# FRAM_with_level_converter_discrete.net
KiCad netlist of a schematic drawn in EAGLE
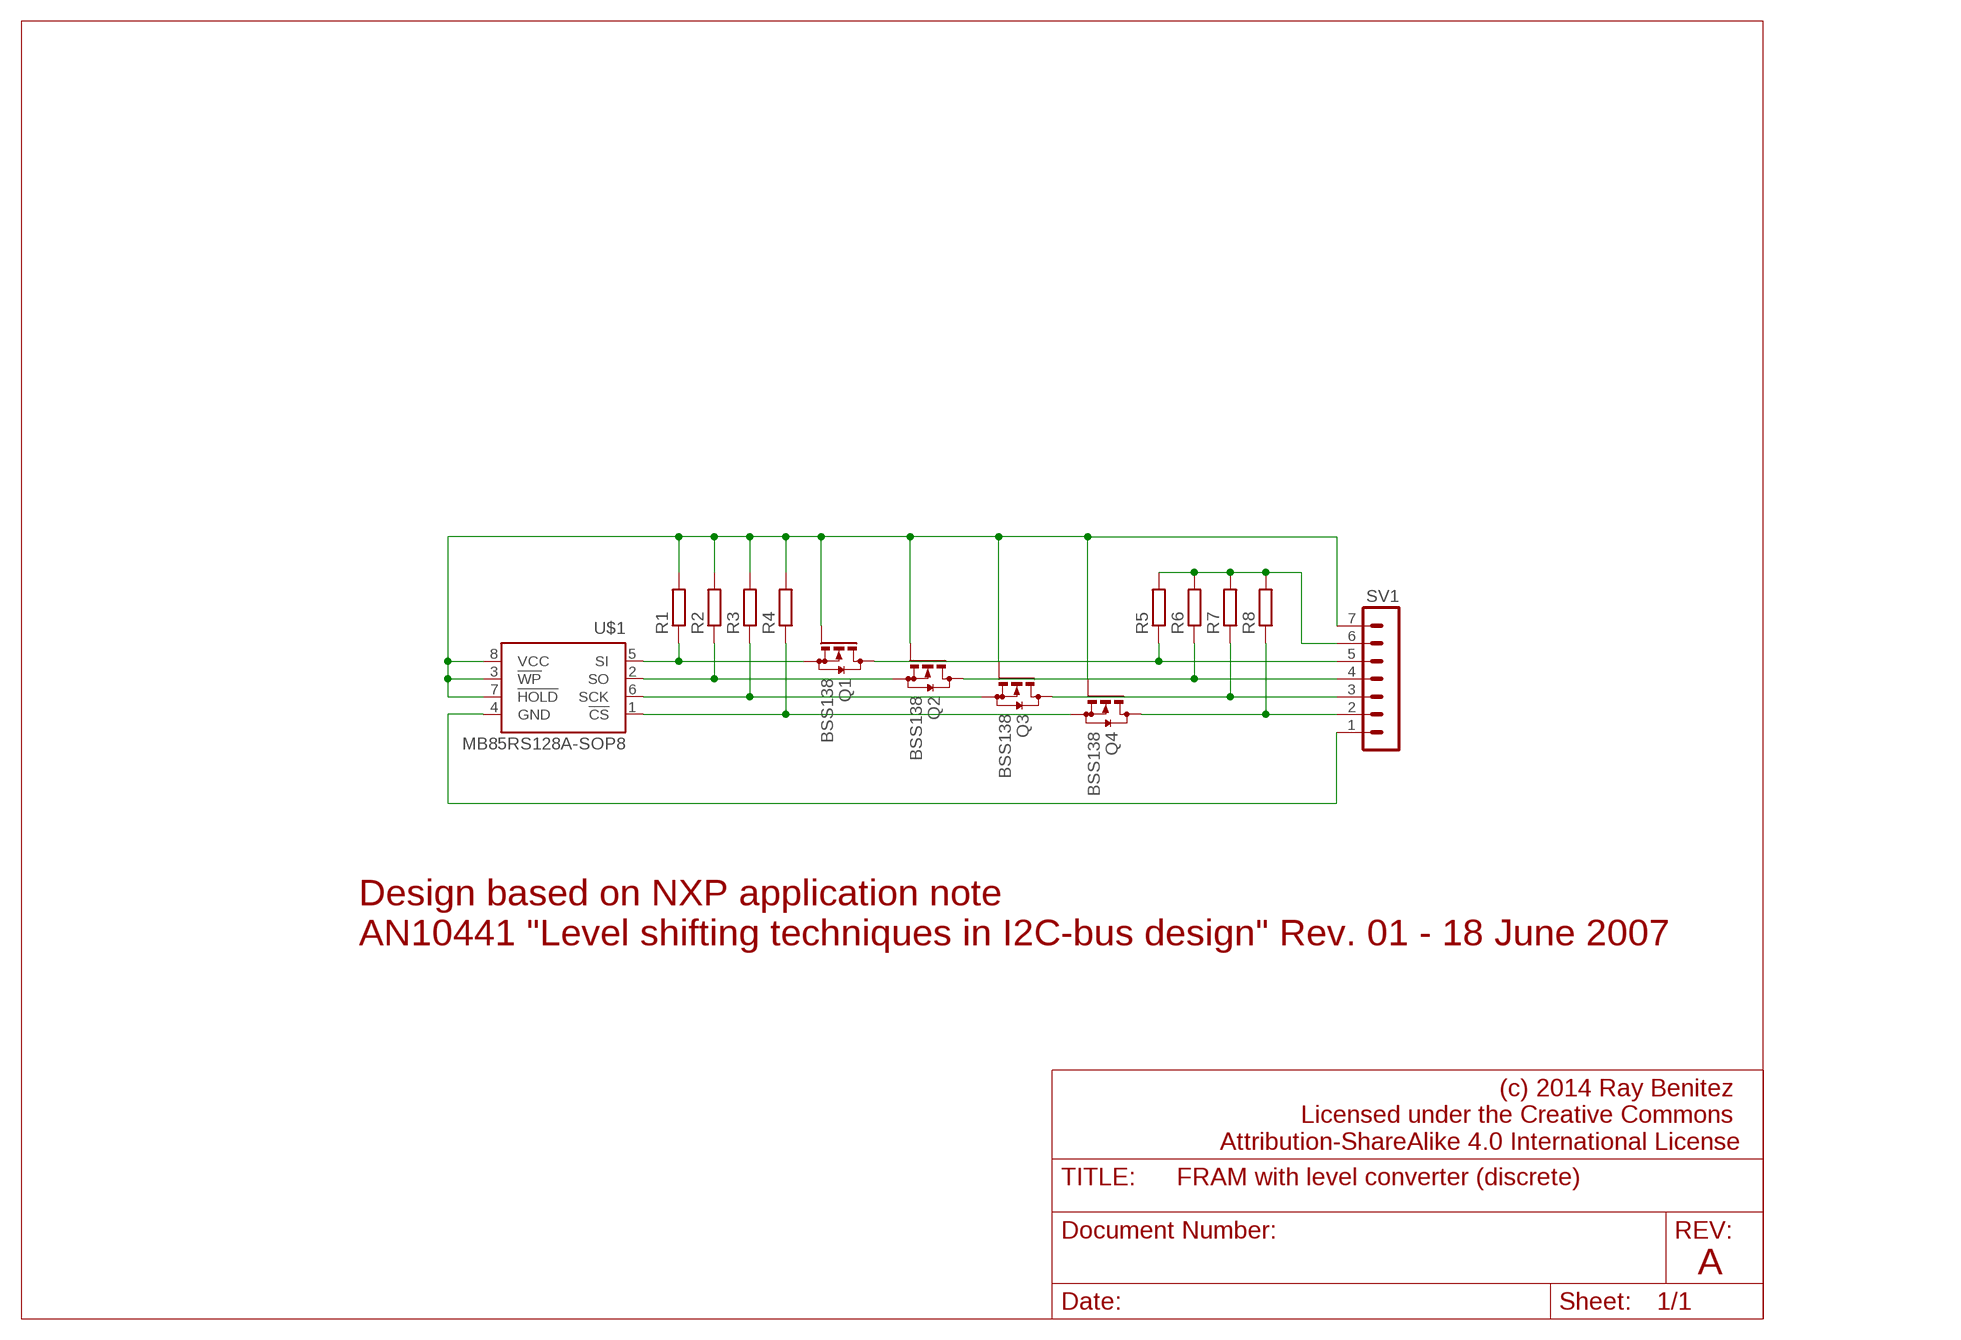
[diagram p0: schematic, sheet 1]

(export (version "E")
  (design (tool "Eeschema 10.0.6"))
  (components
    (comp (ref "Q1")
      (value "BSS138")
      (footprint "eagle-import:SOT23")
      (libsource (lib "eagle-import") (part "BSS138-SOT23"))
    )
    (comp (ref "Q2")
      (value "BSS138")
      (footprint "eagle-import:SOT23")
      (libsource (lib "eagle-import") (part "BSS138-SOT23"))
    )
    (comp (ref "Q3")
      (value "BSS138")
      (footprint "eagle-import:SOT23")
      (libsource (lib "eagle-import") (part "BSS138-SOT23"))
    )
    (comp (ref "Q4")
      (value "BSS138")
      (footprint "eagle-import:SOT23")
      (libsource (lib "eagle-import") (part "BSS138-SOT23"))
    )
    (comp (ref "R1")
      (value "R-EU_R0805")
      (footprint "eagle-import:R0805")
      (libsource (lib "eagle-import") (part "R-EU_R0805"))
    )
    (comp (ref "R2")
      (value "R-EU_R0805")
      (footprint "eagle-import:R0805")
      (libsource (lib "eagle-import") (part "R-EU_R0805"))
    )
    (comp (ref "R3")
      (value "R-EU_R0805")
      (footprint "eagle-import:R0805")
      (libsource (lib "eagle-import") (part "R-EU_R0805"))
    )
    (comp (ref "R4")
      (value "R-EU_R0805")
      (footprint "eagle-import:R0805")
      (libsource (lib "eagle-import") (part "R-EU_R0805"))
    )
    (comp (ref "R5")
      (value "R-EU_R0805")
      (footprint "eagle-import:R0805")
      (libsource (lib "eagle-import") (part "R-EU_R0805"))
    )
    (comp (ref "R6")
      (value "R-EU_R0805")
      (footprint "eagle-import:R0805")
      (libsource (lib "eagle-import") (part "R-EU_R0805"))
    )
    (comp (ref "R7")
      (value "R-EU_R0805")
      (footprint "eagle-import:R0805")
      (libsource (lib "eagle-import") (part "R-EU_R0805"))
    )
    (comp (ref "R8")
      (value "R-EU_R0805")
      (footprint "eagle-import:R0805")
      (libsource (lib "eagle-import") (part "R-EU_R0805"))
    )
    (comp (ref "SV1")
      (value "MA07-1")
      (footprint "eagle-import:MA07-1")
      (libsource (lib "eagle-import") (part "MA07-1"))
    )
    (comp (ref "U$1")
      (value "MB85RS128A-SOP8")
      (footprint "eagle-import:SO08")
      (libsource (lib "eagle-import") (part "MB85RS-SOP8128A"))
    )
  )
  (nets
    (net (code "1") (name "Net-(Q1-D)") (class "Default")
      (node (ref "Q1") (pin "3") (pinfunction "D_3") (pintype "passive"))
      (node (ref "R5") (pin "1") (pinfunction "1_1") (pintype "passive"))
      (node (ref "SV1") (pin "5") (pinfunction "5_5") (pintype "passive"))
    )
    (net (code "2") (name "Net-(Q1-G)") (class "Default")
      (node (ref "Q1") (pin "1") (pinfunction "G_1") (pintype "passive"))
      (node (ref "Q2") (pin "1") (pinfunction "G_1") (pintype "passive"))
      (node (ref "Q3") (pin "1") (pinfunction "G_1") (pintype "passive"))
      (node (ref "Q4") (pin "1") (pinfunction "G_1") (pintype "passive"))
      (node (ref "R1") (pin "2") (pinfunction "2_2") (pintype "passive"))
      (node (ref "R2") (pin "2") (pinfunction "2_2") (pintype "passive"))
      (node (ref "R3") (pin "2") (pinfunction "2_2") (pintype "passive"))
      (node (ref "R4") (pin "2") (pinfunction "2_2") (pintype "passive"))
      (node (ref "SV1") (pin "7") (pinfunction "7_7") (pintype "passive"))
      (node (ref "U$1") (pin "3") (pinfunction "~{WP}_3") (pintype "input"))
      (node (ref "U$1") (pin "7") (pinfunction "~{HOLD}_7") (pintype "input"))
      (node (ref "U$1") (pin "8") (pinfunction "VCC_8") (pintype "power_in"))
    )
    (net (code "3") (name "Net-(Q1-S)") (class "Default")
      (node (ref "Q1") (pin "2") (pinfunction "S_2") (pintype "passive"))
      (node (ref "R1") (pin "1") (pinfunction "1_1") (pintype "passive"))
      (node (ref "U$1") (pin "5") (pinfunction "SI_5") (pintype "input"))
    )
    (net (code "4") (name "Net-(Q2-D)") (class "Default")
      (node (ref "Q2") (pin "3") (pinfunction "D_3") (pintype "passive"))
      (node (ref "R6") (pin "1") (pinfunction "1_1") (pintype "passive"))
      (node (ref "SV1") (pin "4") (pinfunction "4_4") (pintype "passive"))
    )
    (net (code "5") (name "Net-(Q2-S)") (class "Default")
      (node (ref "Q2") (pin "2") (pinfunction "S_2") (pintype "passive"))
      (node (ref "R2") (pin "1") (pinfunction "1_1") (pintype "passive"))
      (node (ref "U$1") (pin "2") (pinfunction "SO_2") (pintype "output"))
    )
    (net (code "6") (name "Net-(Q3-D)") (class "Default")
      (node (ref "Q3") (pin "3") (pinfunction "D_3") (pintype "passive"))
      (node (ref "R7") (pin "1") (pinfunction "1_1") (pintype "passive"))
      (node (ref "SV1") (pin "3") (pinfunction "3_3") (pintype "passive"))
    )
    (net (code "7") (name "Net-(Q3-S)") (class "Default")
      (node (ref "Q3") (pin "2") (pinfunction "S_2") (pintype "passive"))
      (node (ref "R3") (pin "1") (pinfunction "1_1") (pintype "passive"))
      (node (ref "U$1") (pin "6") (pinfunction "SCK_6") (pintype "input"))
    )
    (net (code "8") (name "Net-(Q4-D)") (class "Default")
      (node (ref "Q4") (pin "3") (pinfunction "D_3") (pintype "passive"))
      (node (ref "R8") (pin "1") (pinfunction "1_1") (pintype "passive"))
      (node (ref "SV1") (pin "2") (pinfunction "2_2") (pintype "passive"))
    )
    (net (code "9") (name "Net-(Q4-S)") (class "Default")
      (node (ref "Q4") (pin "2") (pinfunction "S_2") (pintype "passive"))
      (node (ref "R4") (pin "1") (pinfunction "1_1") (pintype "passive"))
      (node (ref "U$1") (pin "1") (pinfunction "~{CS}_1") (pintype "input"))
    )
    (net (code "10") (name "Net-(R5-Pad2)") (class "Default")
      (node (ref "R5") (pin "2") (pinfunction "2_2") (pintype "passive"))
      (node (ref "R6") (pin "2") (pinfunction "2_2") (pintype "passive"))
      (node (ref "R7") (pin "2") (pinfunction "2_2") (pintype "passive"))
      (node (ref "R8") (pin "2") (pinfunction "2_2") (pintype "passive"))
      (node (ref "SV1") (pin "6") (pinfunction "6_6") (pintype "passive"))
    )
    (net (code "11") (name "Net-(U$1-GND)") (class "Default")
      (node (ref "SV1") (pin "1") (pinfunction "1_1") (pintype "passive"))
      (node (ref "U$1") (pin "4") (pinfunction "GND_4") (pintype "power_in"))
    )
  )
)
